# Smart_Water_Meter.net
KiCad netlist of a schematic drawn in EasyEDA Pro
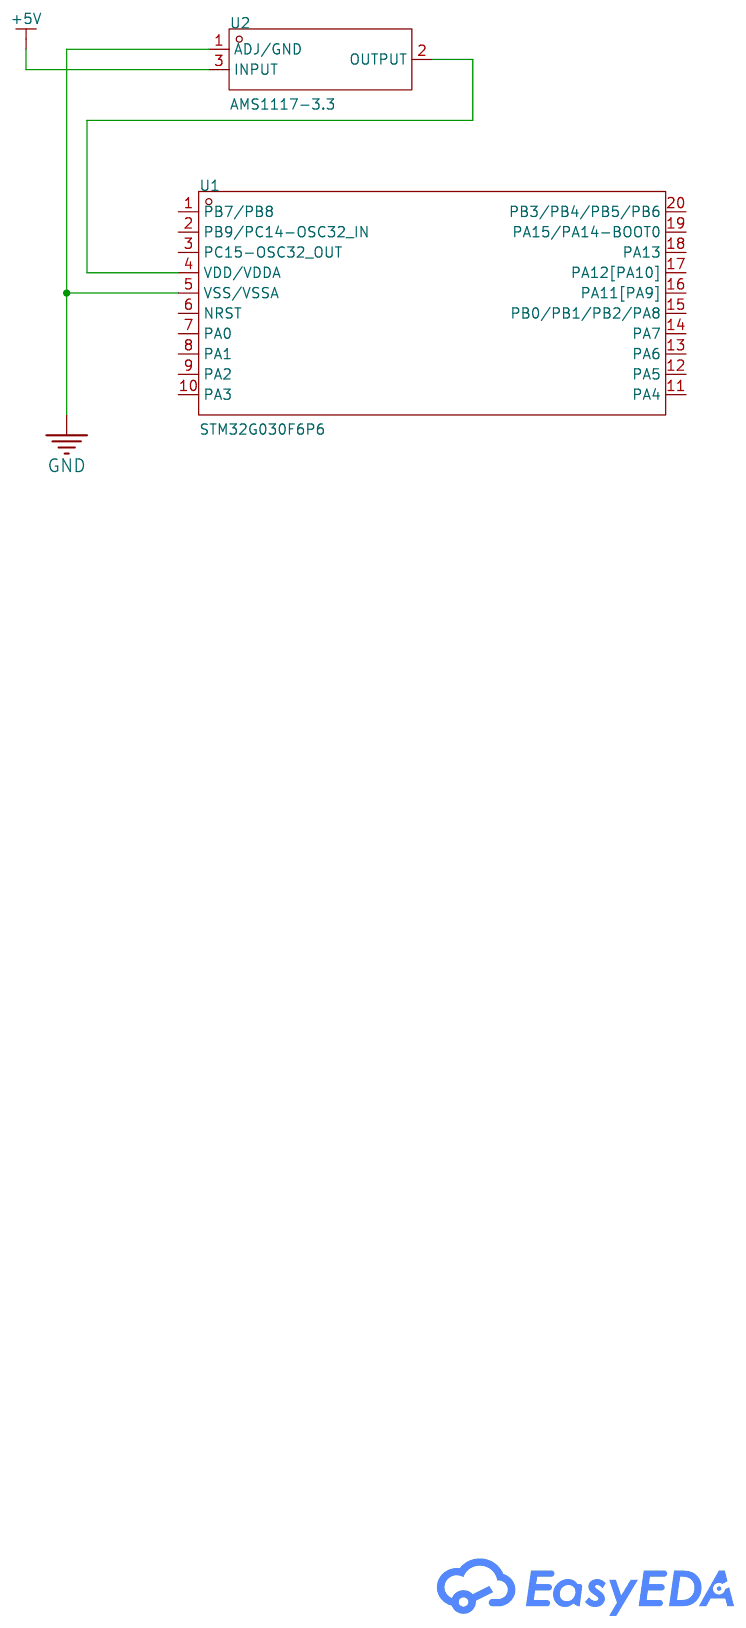
[diagram p0: schematic sheet]

(export (version "E")
  (design (tool "Eeschema 10.0.6"))
  (components
    (comp (ref "U1")
      (value "STM32G030F6P6")
      (footprint "easyedapro:TSSOP-20_L6.5-W4.4-P0.65-LS6.4-BL")
      (fields (field (name "Manufacturer") "ST(意法半导体)"))
      (libsource (lib "easyedapro") (part "STM32G030F6P6"))
    )
    (comp (ref "U2")
      (value "AMS1117-3.3")
      (footprint "easyedapro:TO-252-2_L6.6-W5.6-P2.3-LS9.7")
      (fields (field (name "Manufacturer") "YONGYUTAI(永裕泰)"))
      (libsource (lib "easyedapro") (part "AMS1117-3.3_C41414107"))
    )
  )
  (nets
    (net (code "1") (name "+5V") (class "Default")
      (node (ref "U2") (pin "3") (pinfunction "INPUT_3") (pintype "unspecified"))
    )
    (net (code "2") (name "GND") (class "Default")
      (node (ref "U1") (pin "5") (pinfunction "VSS/VSSA_5") (pintype "unspecified"))
      (node (ref "U2") (pin "1") (pinfunction "ADJ/GND_1") (pintype "unspecified"))
    )
    (net (code "3") (name "Net-(U1-VDD{slash}VDDA)") (class "Default")
      (node (ref "U1") (pin "4") (pinfunction "VDD/VDDA_4") (pintype "unspecified"))
      (node (ref "U2") (pin "2") (pinfunction "OUTPUT_2") (pintype "unspecified"))
    )
    (net (code "4") (name "unconnected-(U1-NRST-Pad6)") (class "Default")
      (node (ref "U1") (pin "6") (pinfunction "NRST_6") (pintype "unspecified"))
    )
    (net (code "5") (name "unconnected-(U1-PA0-Pad7)") (class "Default")
      (node (ref "U1") (pin "7") (pinfunction "PA0_7") (pintype "unspecified"))
    )
    (net (code "6") (name "unconnected-(U1-PA1-Pad8)") (class "Default")
      (node (ref "U1") (pin "8") (pinfunction "PA1_8") (pintype "unspecified"))
    )
    (net (code "7") (name "unconnected-(U1-PA2-Pad9)") (class "Default")
      (node (ref "U1") (pin "9") (pinfunction "PA2_9") (pintype "unspecified"))
    )
    (net (code "8") (name "unconnected-(U1-PA3-Pad10)") (class "Default")
      (node (ref "U1") (pin "10") (pinfunction "PA3_10") (pintype "unspecified"))
    )
    (net (code "9") (name "unconnected-(U1-PA4-Pad11)") (class "Default")
      (node (ref "U1") (pin "11") (pinfunction "PA4_11") (pintype "unspecified"))
    )
    (net (code "10") (name "unconnected-(U1-PA5-Pad12)") (class "Default")
      (node (ref "U1") (pin "12") (pinfunction "PA5_12") (pintype "unspecified"))
    )
    (net (code "11") (name "unconnected-(U1-PA6-Pad13)") (class "Default")
      (node (ref "U1") (pin "13") (pinfunction "PA6_13") (pintype "unspecified"))
    )
    (net (code "12") (name "unconnected-(U1-PA7-Pad14)") (class "Default")
      (node (ref "U1") (pin "14") (pinfunction "PA7_14") (pintype "unspecified"))
    )
    (net (code "13") (name "unconnected-(U1-PA11[PA9]-Pad16)") (class "Default")
      (node (ref "U1") (pin "16") (pinfunction "PA11[PA9]_16") (pintype "unspecified"))
    )
    (net (code "14") (name "unconnected-(U1-PA12[PA10]-Pad17)") (class "Default")
      (node (ref "U1") (pin "17") (pinfunction "PA12[PA10]_17") (pintype "unspecified"))
    )
    (net (code "15") (name "unconnected-(U1-PA13-Pad18)") (class "Default")
      (node (ref "U1") (pin "18") (pinfunction "PA13_18") (pintype "unspecified"))
    )
    (net (code "16") (name "unconnected-(U1-PA15{slash}PA14-BOOT0-Pad19)") (class "Default")
      (node (ref "U1") (pin "19") (pinfunction "PA15/PA14-BOOT0_19") (pintype "unspecified"))
    )
    (net (code "17") (name "unconnected-(U1-PB0{slash}PB1{slash}PB2{slash}PA8-Pad15)") (class "Default")
      (node (ref "U1") (pin "15") (pinfunction "PB0/PB1/PB2/PA8_15") (pintype "unspecified"))
    )
    (net (code "18") (name "unconnected-(U1-PB3{slash}PB4{slash}PB5{slash}PB6-Pad20)") (class "Default")
      (node (ref "U1") (pin "20") (pinfunction "PB3/PB4/PB5/PB6_20") (pintype "unspecified"))
    )
    (net (code "19") (name "unconnected-(U1-PB7{slash}PB8-Pad1)") (class "Default")
      (node (ref "U1") (pin "1") (pinfunction "PB7/PB8_1") (pintype "unspecified"))
    )
    (net (code "20") (name "unconnected-(U1-PB9{slash}PC14-OSC32_IN-Pad2)") (class "Default")
      (node (ref "U1") (pin "2") (pinfunction "PB9/PC14-OSC32_IN_2") (pintype "unspecified"))
    )
    (net (code "21") (name "unconnected-(U1-PC15-OSC32_OUT-Pad3)") (class "Default")
      (node (ref "U1") (pin "3") (pinfunction "PC15-OSC32_OUT_3") (pintype "unspecified"))
    )
  )
)
